# 33K_Transistor_Logic.net
KiCad netlist of a schematic drawn in Altium Designer
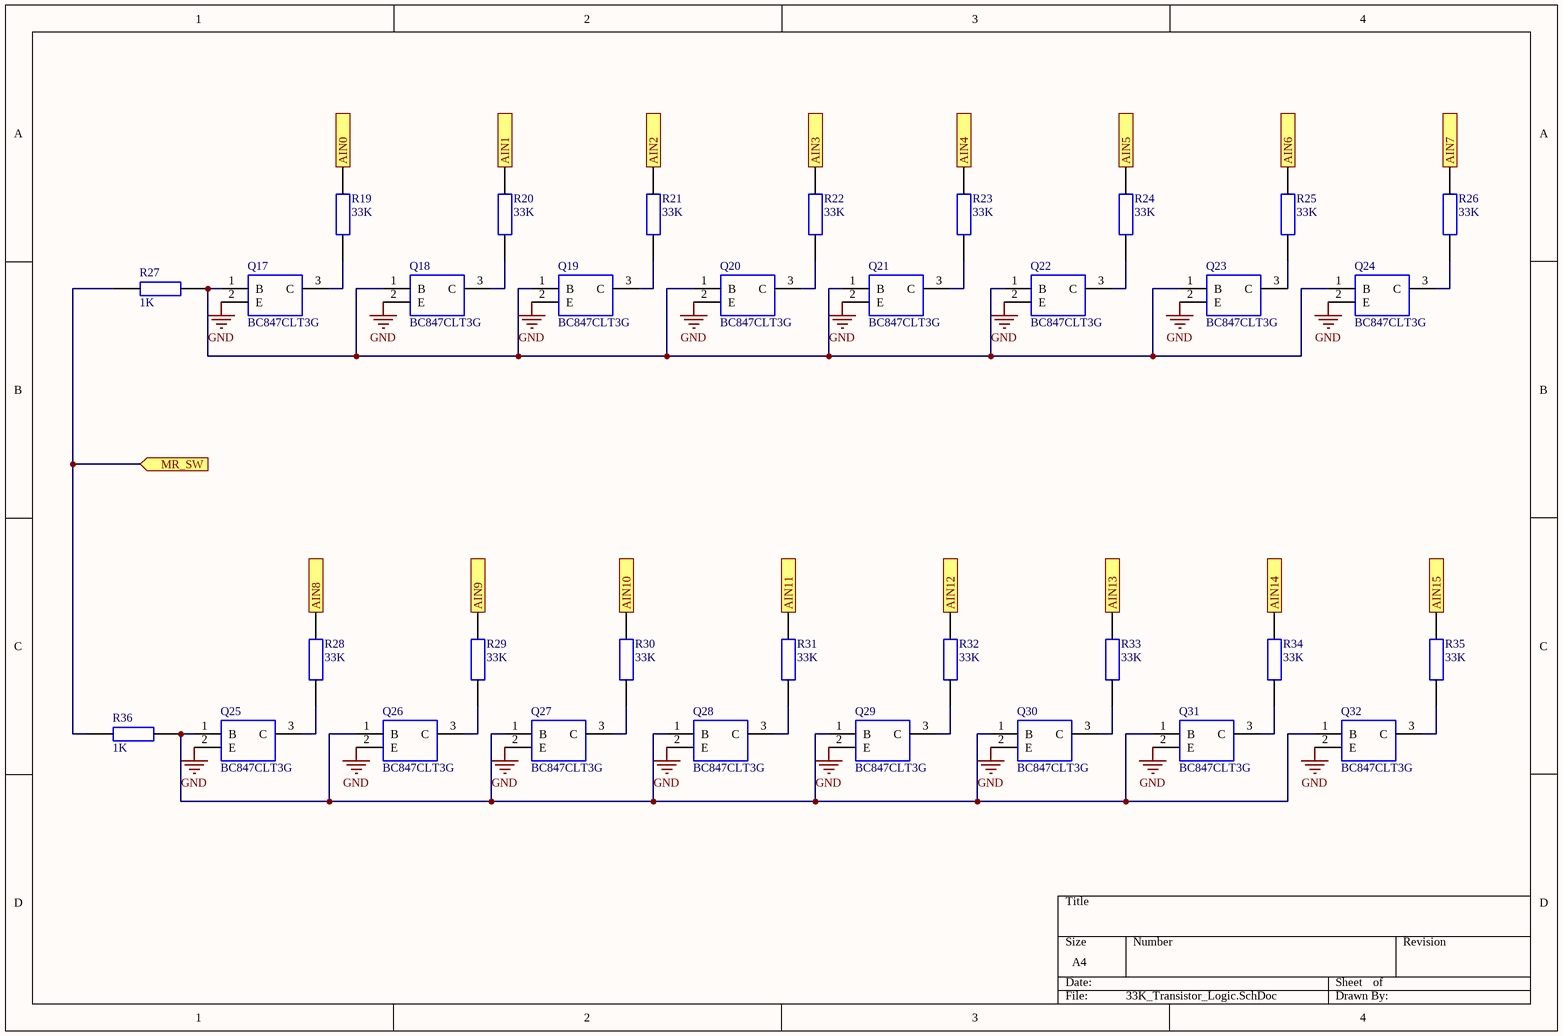
[diagram p0: 33K_Transistor_Logic.SchDoc]

(export (version "E")
  (design (tool "Eeschema 10.0.6"))
  (components
    (comp (ref "Q17")
      (value "BC847CLT3G")
      (footprint "SOT96P237X111-3N")
      (fields (field (name "MOUSER PART NUMBER") "863-BC847CLT3G"))
      (libsource (lib "BC847CLT3G") (part "BC847CLT3G"))
    )
    (comp (ref "Q18")
      (value "BC847CLT3G")
      (footprint "SOT96P237X111-3N")
      (fields (field (name "MOUSER PART NUMBER") "863-BC847CLT3G"))
      (libsource (lib "BC847CLT3G") (part "BC847CLT3G"))
    )
    (comp (ref "Q19")
      (value "BC847CLT3G")
      (footprint "SOT96P237X111-3N")
      (fields (field (name "MOUSER PART NUMBER") "863-BC847CLT3G"))
      (libsource (lib "BC847CLT3G") (part "BC847CLT3G"))
    )
    (comp (ref "Q20")
      (value "BC847CLT3G")
      (footprint "SOT96P237X111-3N")
      (fields (field (name "MOUSER PART NUMBER") "863-BC847CLT3G"))
      (libsource (lib "BC847CLT3G") (part "BC847CLT3G"))
    )
    (comp (ref "Q21")
      (value "BC847CLT3G")
      (footprint "SOT96P237X111-3N")
      (fields (field (name "MOUSER PART NUMBER") "863-BC847CLT3G"))
      (libsource (lib "BC847CLT3G") (part "BC847CLT3G"))
    )
    (comp (ref "Q22")
      (value "BC847CLT3G")
      (footprint "SOT96P237X111-3N")
      (fields (field (name "MOUSER PART NUMBER") "863-BC847CLT3G"))
      (libsource (lib "BC847CLT3G") (part "BC847CLT3G"))
    )
    (comp (ref "Q23")
      (value "BC847CLT3G")
      (footprint "SOT96P237X111-3N")
      (fields (field (name "MOUSER PART NUMBER") "863-BC847CLT3G"))
      (libsource (lib "BC847CLT3G") (part "BC847CLT3G"))
    )
    (comp (ref "Q24")
      (value "BC847CLT3G")
      (footprint "SOT96P237X111-3N")
      (fields (field (name "MOUSER PART NUMBER") "863-BC847CLT3G"))
      (libsource (lib "BC847CLT3G") (part "BC847CLT3G"))
    )
    (comp (ref "Q25")
      (value "BC847CLT3G")
      (footprint "SOT96P237X111-3N")
      (fields (field (name "MOUSER PART NUMBER") "863-BC847CLT3G"))
      (libsource (lib "BC847CLT3G") (part "BC847CLT3G"))
    )
    (comp (ref "Q26")
      (value "BC847CLT3G")
      (footprint "SOT96P237X111-3N")
      (fields (field (name "MOUSER PART NUMBER") "863-BC847CLT3G"))
      (libsource (lib "BC847CLT3G") (part "BC847CLT3G"))
    )
    (comp (ref "Q27")
      (value "BC847CLT3G")
      (footprint "SOT96P237X111-3N")
      (fields (field (name "MOUSER PART NUMBER") "863-BC847CLT3G"))
      (libsource (lib "BC847CLT3G") (part "BC847CLT3G"))
    )
    (comp (ref "Q28")
      (value "BC847CLT3G")
      (footprint "SOT96P237X111-3N")
      (fields (field (name "MOUSER PART NUMBER") "863-BC847CLT3G"))
      (libsource (lib "BC847CLT3G") (part "BC847CLT3G"))
    )
    (comp (ref "Q29")
      (value "BC847CLT3G")
      (footprint "SOT96P237X111-3N")
      (fields (field (name "MOUSER PART NUMBER") "863-BC847CLT3G"))
      (libsource (lib "BC847CLT3G") (part "BC847CLT3G"))
    )
    (comp (ref "Q30")
      (value "BC847CLT3G")
      (footprint "SOT96P237X111-3N")
      (fields (field (name "MOUSER PART NUMBER") "863-BC847CLT3G"))
      (libsource (lib "BC847CLT3G") (part "BC847CLT3G"))
    )
    (comp (ref "Q31")
      (value "BC847CLT3G")
      (footprint "SOT96P237X111-3N")
      (fields (field (name "MOUSER PART NUMBER") "863-BC847CLT3G"))
      (libsource (lib "BC847CLT3G") (part "BC847CLT3G"))
    )
    (comp (ref "Q32")
      (value "BC847CLT3G")
      (footprint "SOT96P237X111-3N")
      (fields (field (name "MOUSER PART NUMBER") "863-BC847CLT3G"))
      (libsource (lib "BC847CLT3G") (part "BC847CLT3G"))
    )
    (comp (ref "R19")
      (value "33K")
      (footprint "RESC1608X55N")
      (description "YAGEO (PHYCOMP) - RC0603FR-07330RL - RES, THICK FILM, 330R, 1%, 0.1W, 0603")
      (fields
        (field (name "MANUFACTURER_PART_NUMBER") "RC0603FR-07330RL")
        (field (name "MOUSER PART NUMBER") "603-RC0603FR-07330RL")
      )
      (libsource (lib "330E_0603") (part "RC0603FR-07330RL"))
    )
    (comp (ref "R20")
      (value "33K")
      (footprint "RESC1608X55N")
      (description "YAGEO (PHYCOMP) - RC0603FR-07330RL - RES, THICK FILM, 330R, 1%, 0.1W, 0603")
      (fields
        (field (name "MANUFACTURER_PART_NUMBER") "RC0603FR-07330RL")
        (field (name "MOUSER PART NUMBER") "603-RC0603FR-07330RL")
      )
      (libsource (lib "330E_0603") (part "RC0603FR-07330RL"))
    )
    (comp (ref "R21")
      (value "33K")
      (footprint "RESC1608X55N")
      (description "YAGEO (PHYCOMP) - RC0603FR-07330RL - RES, THICK FILM, 330R, 1%, 0.1W, 0603")
      (fields
        (field (name "MANUFACTURER_PART_NUMBER") "RC0603FR-07330RL")
        (field (name "MOUSER PART NUMBER") "603-RC0603FR-07330RL")
      )
      (libsource (lib "330E_0603") (part "RC0603FR-07330RL"))
    )
    (comp (ref "R22")
      (value "33K")
      (footprint "RESC1608X55N")
      (description "YAGEO (PHYCOMP) - RC0603FR-07330RL - RES, THICK FILM, 330R, 1%, 0.1W, 0603")
      (fields
        (field (name "MANUFACTURER_PART_NUMBER") "RC0603FR-07330RL")
        (field (name "MOUSER PART NUMBER") "603-RC0603FR-07330RL")
      )
      (libsource (lib "330E_0603") (part "RC0603FR-07330RL"))
    )
    (comp (ref "R23")
      (value "33K")
      (footprint "RESC1608X55N")
      (description "YAGEO (PHYCOMP) - RC0603FR-07330RL - RES, THICK FILM, 330R, 1%, 0.1W, 0603")
      (fields
        (field (name "MANUFACTURER_PART_NUMBER") "RC0603FR-07330RL")
        (field (name "MOUSER PART NUMBER") "603-RC0603FR-07330RL")
      )
      (libsource (lib "330E_0603") (part "RC0603FR-07330RL"))
    )
    (comp (ref "R24")
      (value "33K")
      (footprint "RESC1608X55N")
      (description "YAGEO (PHYCOMP) - RC0603FR-07330RL - RES, THICK FILM, 330R, 1%, 0.1W, 0603")
      (fields
        (field (name "MANUFACTURER_PART_NUMBER") "RC0603FR-07330RL")
        (field (name "MOUSER PART NUMBER") "603-RC0603FR-07330RL")
      )
      (libsource (lib "330E_0603") (part "RC0603FR-07330RL"))
    )
    (comp (ref "R25")
      (value "33K")
      (footprint "RESC1608X55N")
      (description "YAGEO (PHYCOMP) - RC0603FR-07330RL - RES, THICK FILM, 330R, 1%, 0.1W, 0603")
      (fields
        (field (name "MANUFACTURER_PART_NUMBER") "RC0603FR-07330RL")
        (field (name "MOUSER PART NUMBER") "603-RC0603FR-07330RL")
      )
      (libsource (lib "330E_0603") (part "RC0603FR-07330RL"))
    )
    (comp (ref "R26")
      (value "33K")
      (footprint "RESC1608X55N")
      (description "YAGEO (PHYCOMP) - RC0603FR-07330RL - RES, THICK FILM, 330R, 1%, 0.1W, 0603")
      (fields
        (field (name "MANUFACTURER_PART_NUMBER") "RC0603FR-07330RL")
        (field (name "MOUSER PART NUMBER") "603-RC0603FR-07330RL")
      )
      (libsource (lib "330E_0603") (part "RC0603FR-07330RL"))
    )
    (comp (ref "R27")
      (value "1K")
      (footprint "RESC1608X55N")
      (description "YAGEO (PHYCOMP) - RC0603JR-071KL - RES, THICK FILM, 1K, 5%, 0.1W, 0603")
      (fields
        (field (name "MANUFACTURER_PART_NUMBER") "RC0603JR-071KL")
        (field (name "MOUSER PART NUMBER") "603-RC0603JR-071KL")
      )
      (libsource (lib "1K_0603") (part "RC0603JR-071KL"))
    )
    (comp (ref "R28")
      (value "33K")
      (footprint "RESC1608X55N")
      (description "YAGEO (PHYCOMP) - RC0603FR-07330RL - RES, THICK FILM, 330R, 1%, 0.1W, 0603")
      (fields
        (field (name "MANUFACTURER_PART_NUMBER") "RC0603FR-07330RL")
        (field (name "MOUSER PART NUMBER") "603-RC0603FR-07330RL")
      )
      (libsource (lib "330E_0603") (part "RC0603FR-07330RL"))
    )
    (comp (ref "R29")
      (value "33K")
      (footprint "RESC1608X55N")
      (description "YAGEO (PHYCOMP) - RC0603FR-07330RL - RES, THICK FILM, 330R, 1%, 0.1W, 0603")
      (fields
        (field (name "MANUFACTURER_PART_NUMBER") "RC0603FR-07330RL")
        (field (name "MOUSER PART NUMBER") "603-RC0603FR-07330RL")
      )
      (libsource (lib "330E_0603") (part "RC0603FR-07330RL"))
    )
    (comp (ref "R30")
      (value "33K")
      (footprint "RESC1608X55N")
      (description "YAGEO (PHYCOMP) - RC0603FR-07330RL - RES, THICK FILM, 330R, 1%, 0.1W, 0603")
      (fields
        (field (name "MANUFACTURER_PART_NUMBER") "RC0603FR-07330RL")
        (field (name "MOUSER PART NUMBER") "603-RC0603FR-07330RL")
      )
      (libsource (lib "330E_0603") (part "RC0603FR-07330RL"))
    )
    (comp (ref "R31")
      (value "33K")
      (footprint "RESC1608X55N")
      (description "YAGEO (PHYCOMP) - RC0603FR-07330RL - RES, THICK FILM, 330R, 1%, 0.1W, 0603")
      (fields
        (field (name "MANUFACTURER_PART_NUMBER") "RC0603FR-07330RL")
        (field (name "MOUSER PART NUMBER") "603-RC0603FR-07330RL")
      )
      (libsource (lib "330E_0603") (part "RC0603FR-07330RL"))
    )
    (comp (ref "R32")
      (value "33K")
      (footprint "RESC1608X55N")
      (description "YAGEO (PHYCOMP) - RC0603FR-07330RL - RES, THICK FILM, 330R, 1%, 0.1W, 0603")
      (fields
        (field (name "MANUFACTURER_PART_NUMBER") "RC0603FR-07330RL")
        (field (name "MOUSER PART NUMBER") "603-RC0603FR-07330RL")
      )
      (libsource (lib "330E_0603") (part "RC0603FR-07330RL"))
    )
    (comp (ref "R33")
      (value "33K")
      (footprint "RESC1608X55N")
      (description "YAGEO (PHYCOMP) - RC0603FR-07330RL - RES, THICK FILM, 330R, 1%, 0.1W, 0603")
      (fields
        (field (name "MANUFACTURER_PART_NUMBER") "RC0603FR-07330RL")
        (field (name "MOUSER PART NUMBER") "603-RC0603FR-07330RL")
      )
      (libsource (lib "330E_0603") (part "RC0603FR-07330RL"))
    )
    (comp (ref "R34")
      (value "33K")
      (footprint "RESC1608X55N")
      (description "YAGEO (PHYCOMP) - RC0603FR-07330RL - RES, THICK FILM, 330R, 1%, 0.1W, 0603")
      (fields
        (field (name "MANUFACTURER_PART_NUMBER") "RC0603FR-07330RL")
        (field (name "MOUSER PART NUMBER") "603-RC0603FR-07330RL")
      )
      (libsource (lib "330E_0603") (part "RC0603FR-07330RL"))
    )
    (comp (ref "R35")
      (value "33K")
      (footprint "RESC1608X55N")
      (description "YAGEO (PHYCOMP) - RC0603FR-07330RL - RES, THICK FILM, 330R, 1%, 0.1W, 0603")
      (fields
        (field (name "MANUFACTURER_PART_NUMBER") "RC0603FR-07330RL")
        (field (name "MOUSER PART NUMBER") "603-RC0603FR-07330RL")
      )
      (libsource (lib "330E_0603") (part "RC0603FR-07330RL"))
    )
    (comp (ref "R36")
      (value "1K")
      (footprint "RESC1608X55N")
      (description "YAGEO (PHYCOMP) - RC0603JR-071KL - RES, THICK FILM, 1K, 5%, 0.1W, 0603")
      (fields
        (field (name "MANUFACTURER_PART_NUMBER") "RC0603JR-071KL")
        (field (name "MOUSER PART NUMBER") "603-RC0603JR-071KL")
      )
      (libsource (lib "1K_0603") (part "RC0603JR-071KL"))
    )
  )
  (nets
    (net (code "1") (name "/AIN0") (class "Default")
      (node (ref "R19") (pin "2") (pinfunction "2_2") (pintype "passive"))
    )
    (net (code "2") (name "/AIN1") (class "Default")
      (node (ref "R20") (pin "2") (pinfunction "2_2") (pintype "passive"))
    )
    (net (code "3") (name "/AIN2") (class "Default")
      (node (ref "R21") (pin "2") (pinfunction "2_2") (pintype "passive"))
    )
    (net (code "4") (name "/AIN3") (class "Default")
      (node (ref "R22") (pin "2") (pinfunction "2_2") (pintype "passive"))
    )
    (net (code "5") (name "/AIN4") (class "Default")
      (node (ref "R23") (pin "2") (pinfunction "2_2") (pintype "passive"))
    )
    (net (code "6") (name "/AIN5") (class "Default")
      (node (ref "R24") (pin "2") (pinfunction "2_2") (pintype "passive"))
    )
    (net (code "7") (name "/AIN6") (class "Default")
      (node (ref "R25") (pin "2") (pinfunction "2_2") (pintype "passive"))
    )
    (net (code "8") (name "/AIN7") (class "Default")
      (node (ref "R26") (pin "2") (pinfunction "2_2") (pintype "passive"))
    )
    (net (code "9") (name "/AIN8") (class "Default")
      (node (ref "R28") (pin "2") (pinfunction "2_2") (pintype "passive"))
    )
    (net (code "10") (name "/AIN9") (class "Default")
      (node (ref "R29") (pin "2") (pinfunction "2_2") (pintype "passive"))
    )
    (net (code "11") (name "/AIN10") (class "Default")
      (node (ref "R30") (pin "2") (pinfunction "2_2") (pintype "passive"))
    )
    (net (code "12") (name "/AIN11") (class "Default")
      (node (ref "R31") (pin "2") (pinfunction "2_2") (pintype "passive"))
    )
    (net (code "13") (name "/AIN12") (class "Default")
      (node (ref "R32") (pin "2") (pinfunction "2_2") (pintype "passive"))
    )
    (net (code "14") (name "/AIN13") (class "Default")
      (node (ref "R33") (pin "2") (pinfunction "2_2") (pintype "passive"))
    )
    (net (code "15") (name "/AIN14") (class "Default")
      (node (ref "R34") (pin "2") (pinfunction "2_2") (pintype "passive"))
    )
    (net (code "16") (name "/AIN15") (class "Default")
      (node (ref "R35") (pin "2") (pinfunction "2_2") (pintype "passive"))
    )
    (net (code "17") (name "/MR_SW") (class "Default")
      (node (ref "R27") (pin "1") (pinfunction "1_1") (pintype "passive"))
      (node (ref "R36") (pin "1") (pinfunction "1_1") (pintype "passive"))
    )
    (net (code "18") (name "GND") (class "Default")
      (node (ref "Q17") (pin "2") (pinfunction "E_2") (pintype "passive"))
      (node (ref "Q18") (pin "2") (pinfunction "E_2") (pintype "passive"))
      (node (ref "Q19") (pin "2") (pinfunction "E_2") (pintype "passive"))
      (node (ref "Q20") (pin "2") (pinfunction "E_2") (pintype "passive"))
      (node (ref "Q21") (pin "2") (pinfunction "E_2") (pintype "passive"))
      (node (ref "Q22") (pin "2") (pinfunction "E_2") (pintype "passive"))
      (node (ref "Q23") (pin "2") (pinfunction "E_2") (pintype "passive"))
      (node (ref "Q24") (pin "2") (pinfunction "E_2") (pintype "passive"))
      (node (ref "Q25") (pin "2") (pinfunction "E_2") (pintype "passive"))
      (node (ref "Q26") (pin "2") (pinfunction "E_2") (pintype "passive"))
      (node (ref "Q27") (pin "2") (pinfunction "E_2") (pintype "passive"))
      (node (ref "Q28") (pin "2") (pinfunction "E_2") (pintype "passive"))
      (node (ref "Q29") (pin "2") (pinfunction "E_2") (pintype "passive"))
      (node (ref "Q30") (pin "2") (pinfunction "E_2") (pintype "passive"))
      (node (ref "Q31") (pin "2") (pinfunction "E_2") (pintype "passive"))
      (node (ref "Q32") (pin "2") (pinfunction "E_2") (pintype "passive"))
    )
    (net (code "19") (name "Net-(Q17-B)") (class "Default")
      (node (ref "Q17") (pin "1") (pinfunction "B_1") (pintype "passive"))
      (node (ref "Q18") (pin "1") (pinfunction "B_1") (pintype "passive"))
      (node (ref "Q19") (pin "1") (pinfunction "B_1") (pintype "passive"))
      (node (ref "Q20") (pin "1") (pinfunction "B_1") (pintype "passive"))
      (node (ref "Q21") (pin "1") (pinfunction "B_1") (pintype "passive"))
      (node (ref "Q22") (pin "1") (pinfunction "B_1") (pintype "passive"))
      (node (ref "Q23") (pin "1") (pinfunction "B_1") (pintype "passive"))
      (node (ref "Q24") (pin "1") (pinfunction "B_1") (pintype "passive"))
      (node (ref "R27") (pin "2") (pinfunction "2_2") (pintype "passive"))
    )
    (net (code "20") (name "Net-(Q17-C)") (class "Default")
      (node (ref "Q17") (pin "3") (pinfunction "C_3") (pintype "passive"))
      (node (ref "R19") (pin "1") (pinfunction "1_1") (pintype "passive"))
    )
    (net (code "21") (name "Net-(Q18-C)") (class "Default")
      (node (ref "Q18") (pin "3") (pinfunction "C_3") (pintype "passive"))
      (node (ref "R20") (pin "1") (pinfunction "1_1") (pintype "passive"))
    )
    (net (code "22") (name "Net-(Q19-C)") (class "Default")
      (node (ref "Q19") (pin "3") (pinfunction "C_3") (pintype "passive"))
      (node (ref "R21") (pin "1") (pinfunction "1_1") (pintype "passive"))
    )
    (net (code "23") (name "Net-(Q20-C)") (class "Default")
      (node (ref "Q20") (pin "3") (pinfunction "C_3") (pintype "passive"))
      (node (ref "R22") (pin "1") (pinfunction "1_1") (pintype "passive"))
    )
    (net (code "24") (name "Net-(Q21-C)") (class "Default")
      (node (ref "Q21") (pin "3") (pinfunction "C_3") (pintype "passive"))
      (node (ref "R23") (pin "1") (pinfunction "1_1") (pintype "passive"))
    )
    (net (code "25") (name "Net-(Q22-C)") (class "Default")
      (node (ref "Q22") (pin "3") (pinfunction "C_3") (pintype "passive"))
      (node (ref "R24") (pin "1") (pinfunction "1_1") (pintype "passive"))
    )
    (net (code "26") (name "Net-(Q23-C)") (class "Default")
      (node (ref "Q23") (pin "3") (pinfunction "C_3") (pintype "passive"))
      (node (ref "R25") (pin "1") (pinfunction "1_1") (pintype "passive"))
    )
    (net (code "27") (name "Net-(Q24-C)") (class "Default")
      (node (ref "Q24") (pin "3") (pinfunction "C_3") (pintype "passive"))
      (node (ref "R26") (pin "1") (pinfunction "1_1") (pintype "passive"))
    )
    (net (code "28") (name "Net-(Q25-B)") (class "Default")
      (node (ref "Q25") (pin "1") (pinfunction "B_1") (pintype "passive"))
      (node (ref "Q26") (pin "1") (pinfunction "B_1") (pintype "passive"))
      (node (ref "Q27") (pin "1") (pinfunction "B_1") (pintype "passive"))
      (node (ref "Q28") (pin "1") (pinfunction "B_1") (pintype "passive"))
      (node (ref "Q29") (pin "1") (pinfunction "B_1") (pintype "passive"))
      (node (ref "Q30") (pin "1") (pinfunction "B_1") (pintype "passive"))
      (node (ref "Q31") (pin "1") (pinfunction "B_1") (pintype "passive"))
      (node (ref "Q32") (pin "1") (pinfunction "B_1") (pintype "passive"))
      (node (ref "R36") (pin "2") (pinfunction "2_2") (pintype "passive"))
    )
    (net (code "29") (name "Net-(Q25-C)") (class "Default")
      (node (ref "Q25") (pin "3") (pinfunction "C_3") (pintype "passive"))
      (node (ref "R28") (pin "1") (pinfunction "1_1") (pintype "passive"))
    )
    (net (code "30") (name "Net-(Q26-C)") (class "Default")
      (node (ref "Q26") (pin "3") (pinfunction "C_3") (pintype "passive"))
      (node (ref "R29") (pin "1") (pinfunction "1_1") (pintype "passive"))
    )
    (net (code "31") (name "Net-(Q27-C)") (class "Default")
      (node (ref "Q27") (pin "3") (pinfunction "C_3") (pintype "passive"))
      (node (ref "R30") (pin "1") (pinfunction "1_1") (pintype "passive"))
    )
    (net (code "32") (name "Net-(Q28-C)") (class "Default")
      (node (ref "Q28") (pin "3") (pinfunction "C_3") (pintype "passive"))
      (node (ref "R31") (pin "1") (pinfunction "1_1") (pintype "passive"))
    )
    (net (code "33") (name "Net-(Q29-C)") (class "Default")
      (node (ref "Q29") (pin "3") (pinfunction "C_3") (pintype "passive"))
      (node (ref "R32") (pin "1") (pinfunction "1_1") (pintype "passive"))
    )
    (net (code "34") (name "Net-(Q30-C)") (class "Default")
      (node (ref "Q30") (pin "3") (pinfunction "C_3") (pintype "passive"))
      (node (ref "R33") (pin "1") (pinfunction "1_1") (pintype "passive"))
    )
    (net (code "35") (name "Net-(Q31-C)") (class "Default")
      (node (ref "Q31") (pin "3") (pinfunction "C_3") (pintype "passive"))
      (node (ref "R34") (pin "1") (pinfunction "1_1") (pintype "passive"))
    )
    (net (code "36") (name "Net-(Q32-C)") (class "Default")
      (node (ref "Q32") (pin "3") (pinfunction "C_3") (pintype "passive"))
      (node (ref "R35") (pin "1") (pinfunction "1_1") (pintype "passive"))
    )
  )
)
